# SmartPwm_v1.net
KiCad netlist of a schematic drawn in EAGLE
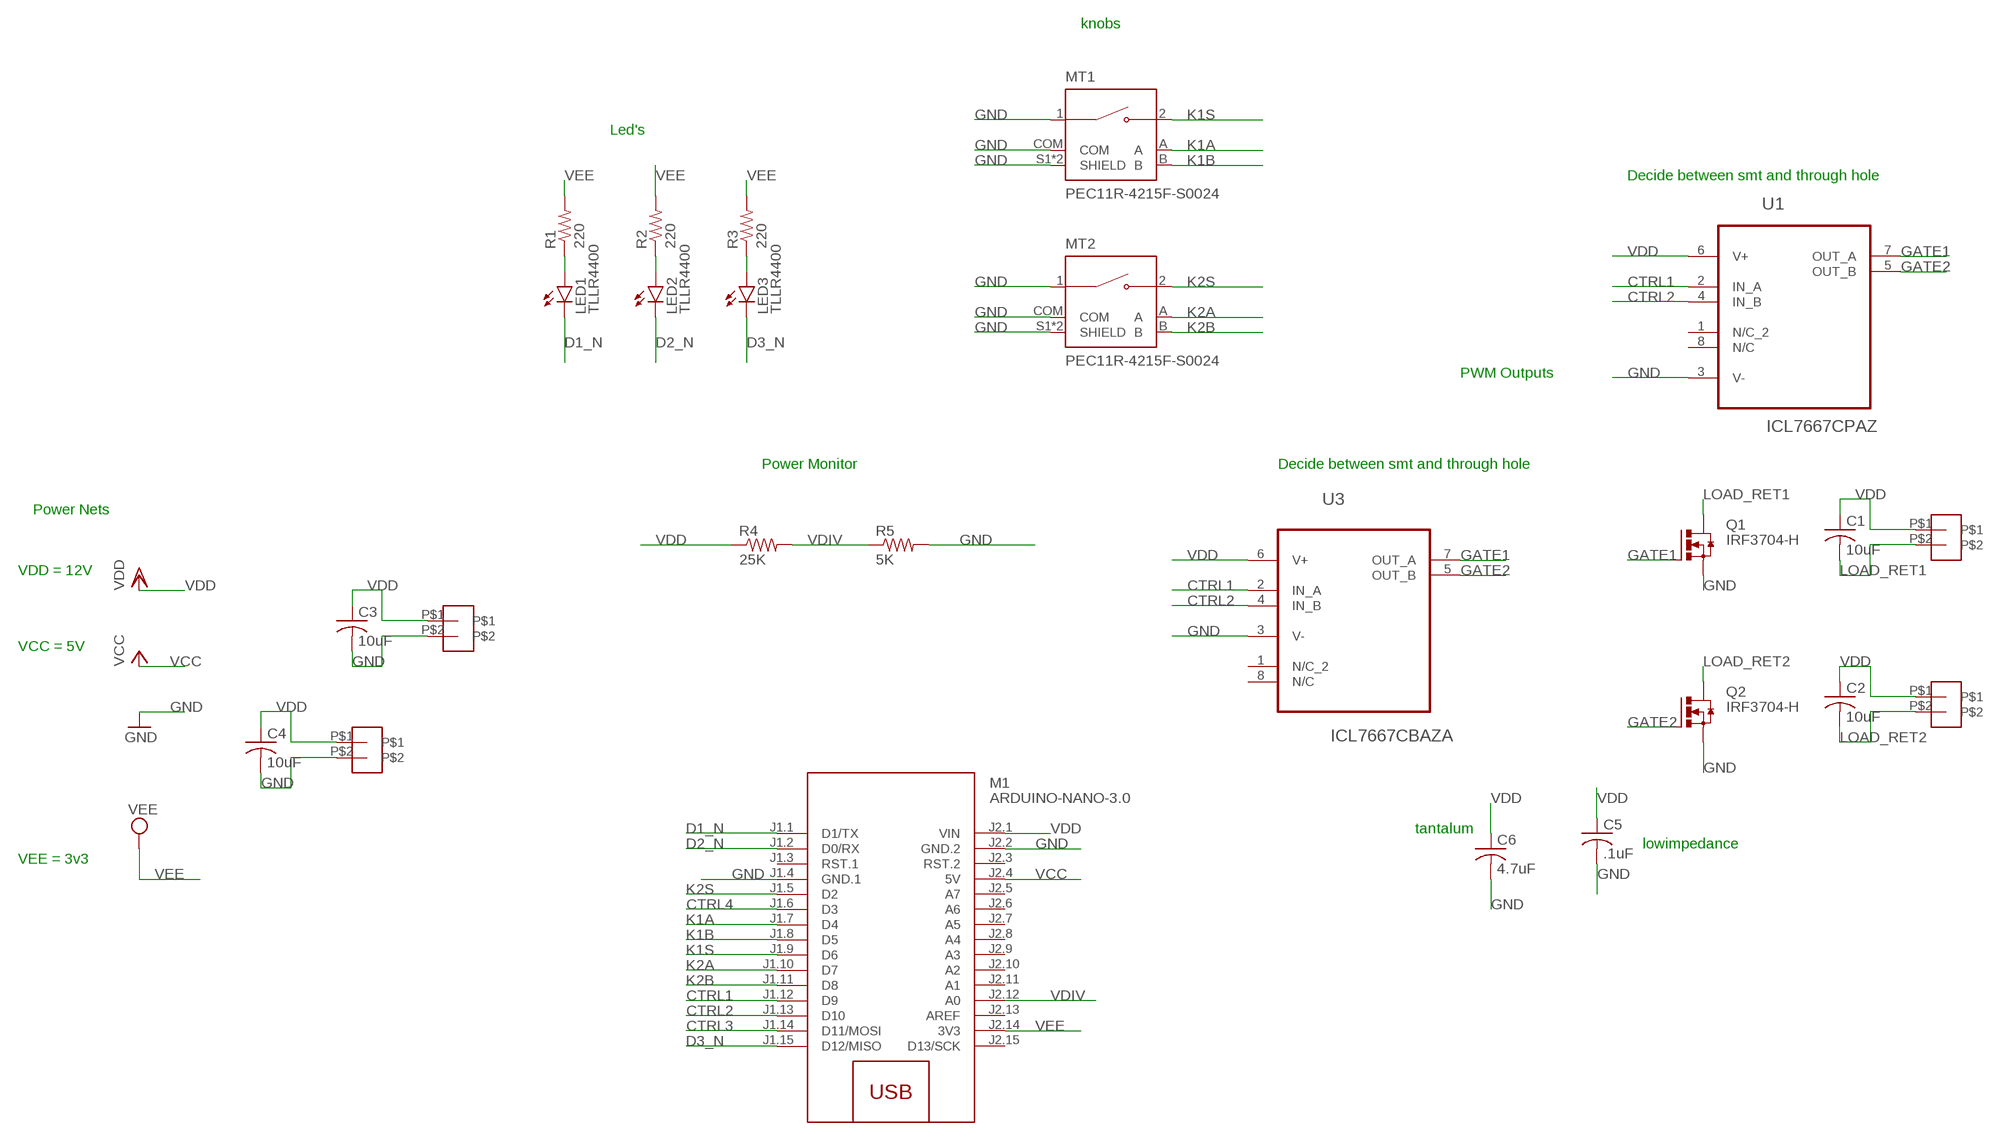
[diagram p0: schematic, sheet 1]

(export (version "E")
  (design (tool "Eeschema 10.0.6"))
  (components
    (comp (ref "C1")
      (value "10uF")
      (footprint "eagle-import:C025-024X044")
      (libsource (lib "eagle-import") (part "C-US025-024X044"))
    )
    (comp (ref "C2")
      (value "10uF")
      (footprint "eagle-import:C025-024X044")
      (libsource (lib "eagle-import") (part "C-US025-024X044"))
    )
    (comp (ref "C3")
      (value "10uF")
      (footprint "eagle-import:C025-024X044")
      (libsource (lib "eagle-import") (part "C-US025-024X044"))
    )
    (comp (ref "C4")
      (value "10uF")
      (footprint "eagle-import:C025-024X044")
      (libsource (lib "eagle-import") (part "C-US025-024X044"))
    )
    (comp (ref "C5")
      (value ".1uF")
      (footprint "eagle-import:C025-024X044")
      (libsource (lib "eagle-import") (part "C-US025-024X044"))
    )
    (comp (ref "C6")
      (value "4.7uF")
      (footprint "eagle-import:C025-024X044")
      (libsource (lib "eagle-import") (part "C-US025-024X044"))
    )
    (comp (ref "LED1")
      (value "TLLR4400")
      (footprint "eagle-import:LED3MM")
      (fields (field (name "MF") "VISHAY SEMICONDUCTOR"))
      (libsource (lib "eagle-import") (part "TLLR4400"))
    )
    (comp (ref "LED2")
      (value "TLLR4400")
      (footprint "eagle-import:LED3MM")
      (fields (field (name "MF") "VISHAY SEMICONDUCTOR"))
      (libsource (lib "eagle-import") (part "TLLR4400"))
    )
    (comp (ref "LED3")
      (value "TLLR4400")
      (footprint "eagle-import:LED3MM")
      (fields (field (name "MF") "VISHAY SEMICONDUCTOR"))
      (libsource (lib "eagle-import") (part "TLLR4400"))
    )
    (comp (ref "M1")
      (value "ARDUINO-NANO-3.0")
      (footprint "eagle-import:ARDUINO-NANO-3.0")
      (libsource (lib "eagle-import") (part "ARDUINO-NANO-3.0"))
    )
    (comp (ref "MT1")
      (value "PEC11R-4215F-S0024")
      (footprint "eagle-import:XDCR_PEC11R-4215F-S0024")
      (fields (field (name "MF") "Bourns"))
      (libsource (lib "eagle-import") (part "PEC11R-4215F-S0024"))
    )
    (comp (ref "MT2")
      (value "PEC11R-4215F-S0024")
      (footprint "eagle-import:XDCR_PEC11R-4215F-S0024")
      (fields (field (name "MF") "Bourns"))
      (libsource (lib "eagle-import") (part "PEC11R-4215F-S0024"))
    )
    (comp (ref "Q1")
      (value "IRF3704-H")
      (footprint "eagle-import:TO220BH")
      (libsource (lib "eagle-import") (part "IRF3704-H"))
    )
    (comp (ref "Q2")
      (value "IRF3704-H")
      (footprint "eagle-import:TO220BH")
      (libsource (lib "eagle-import") (part "IRF3704-H"))
    )
    (comp (ref "R1")
      (value "220")
      (footprint "eagle-import:0207_10")
      (libsource (lib "eagle-import") (part "R-US_0207/10"))
    )
    (comp (ref "R2")
      (value "220")
      (footprint "eagle-import:0207_10")
      (libsource (lib "eagle-import") (part "R-US_0207/10"))
    )
    (comp (ref "R3")
      (value "220")
      (footprint "eagle-import:0207_10")
      (libsource (lib "eagle-import") (part "R-US_0207/10"))
    )
    (comp (ref "R4")
      (value "25K")
      (footprint "eagle-import:0207_10")
      (libsource (lib "eagle-import") (part "R-US_0207/10"))
    )
    (comp (ref "R5")
      (value "5K")
      (footprint "eagle-import:0207_10")
      (libsource (lib "eagle-import") (part "R-US_0207/10"))
    )
    (comp (ref "U$1")
      (value "TB002-500-P02")
      (footprint "eagle-import:TB002-500-P02")
      (libsource (lib "eagle-import") (part "TB002-500-P02"))
    )
    (comp (ref "U$2")
      (value "TB002-500-P02")
      (footprint "eagle-import:TB002-500-P02")
      (libsource (lib "eagle-import") (part "TB002-500-P02"))
    )
    (comp (ref "U$5")
      (value "TB002-500-P02")
      (footprint "eagle-import:TB002-500-P02")
      (libsource (lib "eagle-import") (part "TB002-500-P02"))
    )
    (comp (ref "U$8")
      (value "TB002-500-P02")
      (footprint "eagle-import:TB002-500-P02")
      (libsource (lib "eagle-import") (part "TB002-500-P02"))
    )
    (comp (ref "U1")
      (value "ICL7667CPAZ")
      (footprint "eagle-import:DIP254P762X533-8")
      (fields (field (name "MF") "Renesas Electronics America Inc"))
      (libsource (lib "eagle-import") (part "ICL7667CPAZ"))
    )
    (comp (ref "U3")
      (value "ICL7667CBAZA")
      (footprint "eagle-import:SOIC127P600X175-8N")
      (fields (field (name "MF") "Renesas Electronics America Inc"))
      (libsource (lib "eagle-import") (part "ICL7667CBAZA"))
    )
  )
  (nets
    (net (code "1") (name "/CTRL1") (class "Default")
      (node (ref "M1") (pin "J1.12") (pinfunction "D9_J1.12") (pintype "bidirectional"))
      (node (ref "U1") (pin "2") (pinfunction "IN_A_2") (pintype "input"))
      (node (ref "U3") (pin "2") (pinfunction "IN_A_2") (pintype "input"))
    )
    (net (code "2") (name "/CTRL2") (class "Default")
      (node (ref "M1") (pin "J1.13") (pinfunction "D10_J1.13") (pintype "bidirectional"))
      (node (ref "U1") (pin "4") (pinfunction "IN_B_4") (pintype "input"))
      (node (ref "U3") (pin "4") (pinfunction "IN_B_4") (pintype "input"))
    )
    (net (code "3") (name "/CTRL3") (class "Default")
      (node (ref "M1") (pin "J1.14") (pinfunction "D11/MOSI_J1.14") (pintype "bidirectional"))
    )
    (net (code "4") (name "/CTRL4") (class "Default")
      (node (ref "M1") (pin "J1.6") (pinfunction "D3_J1.6") (pintype "bidirectional"))
    )
    (net (code "5") (name "/D1_N") (class "Default")
      (node (ref "LED1") (pin "K") (pinfunction "C_K") (pintype "passive"))
      (node (ref "M1") (pin "J1.1") (pinfunction "D1/TX_J1.1") (pintype "bidirectional"))
    )
    (net (code "6") (name "/D2_N") (class "Default")
      (node (ref "LED2") (pin "K") (pinfunction "C_K") (pintype "passive"))
      (node (ref "M1") (pin "J1.2") (pinfunction "D0/RX_J1.2") (pintype "bidirectional"))
    )
    (net (code "7") (name "/D3_N") (class "Default")
      (node (ref "LED3") (pin "K") (pinfunction "C_K") (pintype "passive"))
      (node (ref "M1") (pin "J1.15") (pinfunction "D12/MISO_J1.15") (pintype "bidirectional"))
    )
    (net (code "8") (name "/GATE1") (class "Default")
      (node (ref "Q1") (pin "G") (pinfunction "G_G") (pintype "passive"))
      (node (ref "U1") (pin "7") (pinfunction "OUT_A_7") (pintype "output"))
      (node (ref "U3") (pin "7") (pinfunction "OUT_A_7") (pintype "output"))
    )
    (net (code "9") (name "/GATE2") (class "Default")
      (node (ref "Q2") (pin "G") (pinfunction "G_G") (pintype "passive"))
      (node (ref "U1") (pin "5") (pinfunction "OUT_B_5") (pintype "output"))
      (node (ref "U3") (pin "5") (pinfunction "OUT_B_5") (pintype "output"))
    )
    (net (code "10") (name "/K1A") (class "Default")
      (node (ref "M1") (pin "J1.7") (pinfunction "D4_J1.7") (pintype "bidirectional"))
      (node (ref "MT1") (pin "A") (pinfunction "A_A") (pintype "passive"))
    )
    (net (code "11") (name "/K1B") (class "Default")
      (node (ref "M1") (pin "J1.8") (pinfunction "D5_J1.8") (pintype "bidirectional"))
      (node (ref "MT1") (pin "B") (pinfunction "B_B") (pintype "passive"))
    )
    (net (code "12") (name "/K1S") (class "Default")
      (node (ref "M1") (pin "J1.9") (pinfunction "D6_J1.9") (pintype "bidirectional"))
      (node (ref "MT1") (pin "2") (pinfunction "2_2") (pintype "passive"))
    )
    (net (code "13") (name "/K2A") (class "Default")
      (node (ref "M1") (pin "J1.10") (pinfunction "D7_J1.10") (pintype "bidirectional"))
      (node (ref "MT2") (pin "A") (pinfunction "A_A") (pintype "passive"))
    )
    (net (code "14") (name "/K2B") (class "Default")
      (node (ref "M1") (pin "J1.11") (pinfunction "D8_J1.11") (pintype "bidirectional"))
      (node (ref "MT2") (pin "B") (pinfunction "B_B") (pintype "passive"))
    )
    (net (code "15") (name "/K2S") (class "Default")
      (node (ref "M1") (pin "J1.5") (pinfunction "D2_J1.5") (pintype "bidirectional"))
      (node (ref "MT2") (pin "2") (pinfunction "2_2") (pintype "passive"))
    )
    (net (code "16") (name "/LOAD_RET1") (class "Default")
      (node (ref "C1") (pin "2") (pinfunction "2_2") (pintype "passive"))
      (node (ref "Q1") (pin "D") (pinfunction "D_D") (pintype "passive"))
      (node (ref "U$1") (pin "P$2") (pinfunction "P$2_P$2") (pintype "bidirectional"))
    )
    (net (code "17") (name "/LOAD_RET2") (class "Default")
      (node (ref "C2") (pin "2") (pinfunction "2_2") (pintype "passive"))
      (node (ref "Q2") (pin "D") (pinfunction "D_D") (pintype "passive"))
      (node (ref "U$2") (pin "P$2") (pinfunction "P$2_P$2") (pintype "bidirectional"))
    )
    (net (code "18") (name "/VDIV") (class "Default")
      (node (ref "M1") (pin "J2.12") (pinfunction "A0_J2.12") (pintype "bidirectional"))
      (node (ref "R4") (pin "2") (pinfunction "2_2") (pintype "passive"))
      (node (ref "R5") (pin "1") (pinfunction "1_1") (pintype "passive"))
    )
    (net (code "19") (name "GND") (class "Default")
      (node (ref "C3") (pin "2") (pinfunction "2_2") (pintype "passive"))
      (node (ref "C4") (pin "2") (pinfunction "2_2") (pintype "passive"))
      (node (ref "C5") (pin "2") (pinfunction "2_2") (pintype "passive"))
      (node (ref "C6") (pin "2") (pinfunction "2_2") (pintype "passive"))
      (node (ref "M1") (pin "J1.4") (pinfunction "GND.1_J1.4") (pintype "power_in"))
      (node (ref "M1") (pin "J2.2") (pinfunction "GND.2_J2.2") (pintype "power_in"))
      (node (ref "MT1") (pin "1") (pinfunction "1_1") (pintype "passive"))
      (node (ref "MT1") (pin "COM") (pinfunction "COM_COM") (pintype "passive"))
      (node (ref "MT1") (pin "S1") (pinfunction "SHIELD_S1") (pintype "passive"))
      (node (ref "MT1") (pin "S2") (pinfunction "SHIELD_S2") (pintype "passive"))
      (node (ref "MT2") (pin "1") (pinfunction "1_1") (pintype "passive"))
      (node (ref "MT2") (pin "COM") (pinfunction "COM_COM") (pintype "passive"))
      (node (ref "MT2") (pin "S1") (pinfunction "SHIELD_S1") (pintype "passive"))
      (node (ref "MT2") (pin "S2") (pinfunction "SHIELD_S2") (pintype "passive"))
      (node (ref "Q1") (pin "S") (pinfunction "S_S") (pintype "passive"))
      (node (ref "Q2") (pin "S") (pinfunction "S_S") (pintype "passive"))
      (node (ref "R5") (pin "2") (pinfunction "2_2") (pintype "passive"))
      (node (ref "U$5") (pin "P$2") (pinfunction "P$2_P$2") (pintype "bidirectional"))
      (node (ref "U$8") (pin "P$2") (pinfunction "P$2_P$2") (pintype "bidirectional"))
      (node (ref "U1") (pin "3") (pinfunction "V-_3") (pintype "power_in"))
      (node (ref "U3") (pin "3") (pinfunction "V-_3") (pintype "power_in"))
    )
    (net (code "20") (name "Net-(LED1-PadA)") (class "Default")
      (node (ref "LED1") (pin "A") (pinfunction "A_A") (pintype "passive"))
      (node (ref "R1") (pin "1") (pinfunction "1_1") (pintype "passive"))
    )
    (net (code "21") (name "Net-(LED2-PadA)") (class "Default")
      (node (ref "LED2") (pin "A") (pinfunction "A_A") (pintype "passive"))
      (node (ref "R2") (pin "1") (pinfunction "1_1") (pintype "passive"))
    )
    (net (code "22") (name "Net-(LED3-PadA)") (class "Default")
      (node (ref "LED3") (pin "A") (pinfunction "A_A") (pintype "passive"))
      (node (ref "R3") (pin "1") (pinfunction "1_1") (pintype "passive"))
    )
    (net (code "23") (name "VCC") (class "Default")
      (node (ref "M1") (pin "J2.4") (pinfunction "5V_J2.4") (pintype "power_in"))
    )
    (net (code "24") (name "VDD") (class "Default")
      (node (ref "C1") (pin "1") (pinfunction "1_1") (pintype "passive"))
      (node (ref "C2") (pin "1") (pinfunction "1_1") (pintype "passive"))
      (node (ref "C3") (pin "1") (pinfunction "1_1") (pintype "passive"))
      (node (ref "C4") (pin "1") (pinfunction "1_1") (pintype "passive"))
      (node (ref "C5") (pin "1") (pinfunction "1_1") (pintype "passive"))
      (node (ref "C6") (pin "1") (pinfunction "1_1") (pintype "passive"))
      (node (ref "M1") (pin "J2.1") (pinfunction "VIN_J2.1") (pintype "power_in"))
      (node (ref "R4") (pin "1") (pinfunction "1_1") (pintype "passive"))
      (node (ref "U$1") (pin "P$1") (pinfunction "P$1_P$1") (pintype "bidirectional"))
      (node (ref "U$2") (pin "P$1") (pinfunction "P$1_P$1") (pintype "bidirectional"))
      (node (ref "U$5") (pin "P$1") (pinfunction "P$1_P$1") (pintype "bidirectional"))
      (node (ref "U$8") (pin "P$1") (pinfunction "P$1_P$1") (pintype "bidirectional"))
      (node (ref "U1") (pin "6") (pinfunction "V+_6") (pintype "power_in"))
      (node (ref "U3") (pin "6") (pinfunction "V+_6") (pintype "power_in"))
    )
    (net (code "25") (name "VEE") (class "Default")
      (node (ref "M1") (pin "J2.14") (pinfunction "3V3_J2.14") (pintype "power_in"))
      (node (ref "R1") (pin "2") (pinfunction "2_2") (pintype "passive"))
      (node (ref "R2") (pin "2") (pinfunction "2_2") (pintype "passive"))
      (node (ref "R3") (pin "2") (pinfunction "2_2") (pintype "passive"))
    )
    (net (code "26") (name "unconnected-(M1-A1-PadJ2.11)") (class "Default")
      (node (ref "M1") (pin "J2.11") (pinfunction "A1_J2.11") (pintype "bidirectional"))
    )
    (net (code "27") (name "unconnected-(M1-A2-PadJ2.10)") (class "Default")
      (node (ref "M1") (pin "J2.10") (pinfunction "A2_J2.10") (pintype "bidirectional"))
    )
    (net (code "28") (name "unconnected-(M1-A3-PadJ2.9)") (class "Default")
      (node (ref "M1") (pin "J2.9") (pinfunction "A3_J2.9") (pintype "bidirectional"))
    )
    (net (code "29") (name "unconnected-(M1-A4-PadJ2.8)") (class "Default")
      (node (ref "M1") (pin "J2.8") (pinfunction "A4_J2.8") (pintype "bidirectional"))
    )
    (net (code "30") (name "unconnected-(M1-A5-PadJ2.7)") (class "Default")
      (node (ref "M1") (pin "J2.7") (pinfunction "A5_J2.7") (pintype "bidirectional"))
    )
    (net (code "31") (name "unconnected-(M1-A6-PadJ2.6)") (class "Default")
      (node (ref "M1") (pin "J2.6") (pinfunction "A6_J2.6") (pintype "bidirectional"))
    )
    (net (code "32") (name "unconnected-(M1-A7-PadJ2.5)") (class "Default")
      (node (ref "M1") (pin "J2.5") (pinfunction "A7_J2.5") (pintype "bidirectional"))
    )
    (net (code "33") (name "unconnected-(M1-AREF-PadJ2.13)") (class "Default")
      (node (ref "M1") (pin "J2.13") (pinfunction "AREF_J2.13") (pintype "bidirectional"))
    )
    (net (code "34") (name "unconnected-(M1-D13{slash}SCK-PadJ2.15)") (class "Default")
      (node (ref "M1") (pin "J2.15") (pinfunction "D13/SCK_J2.15") (pintype "bidirectional"))
    )
    (net (code "35") (name "unconnected-(M1-RST.1-PadJ1.3)") (class "Default")
      (node (ref "M1") (pin "J1.3") (pinfunction "RST.1_J1.3") (pintype "bidirectional"))
    )
    (net (code "36") (name "unconnected-(M1-RST.2-PadJ2.3)") (class "Default")
      (node (ref "M1") (pin "J2.3") (pinfunction "RST.2_J2.3") (pintype "bidirectional"))
    )
    (net (code "37") (name "unconnected-(U1-N{slash}C-Pad8)") (class "Default")
      (node (ref "U1") (pin "8") (pinfunction "N/C_8") (pintype "no_connect"))
    )
    (net (code "38") (name "unconnected-(U1-N{slash}C_2-Pad1)") (class "Default")
      (node (ref "U1") (pin "1") (pinfunction "N/C_2_1") (pintype "no_connect"))
    )
    (net (code "39") (name "unconnected-(U3-N{slash}C-Pad8)") (class "Default")
      (node (ref "U3") (pin "8") (pinfunction "N/C_8") (pintype "no_connect"))
    )
    (net (code "40") (name "unconnected-(U3-N{slash}C_2-Pad1)") (class "Default")
      (node (ref "U3") (pin "1") (pinfunction "N/C_2_1") (pintype "no_connect"))
    )
  )
)
